# Motor3_PCIe.net
KiCad netlist of a schematic drawn in Altium Designer
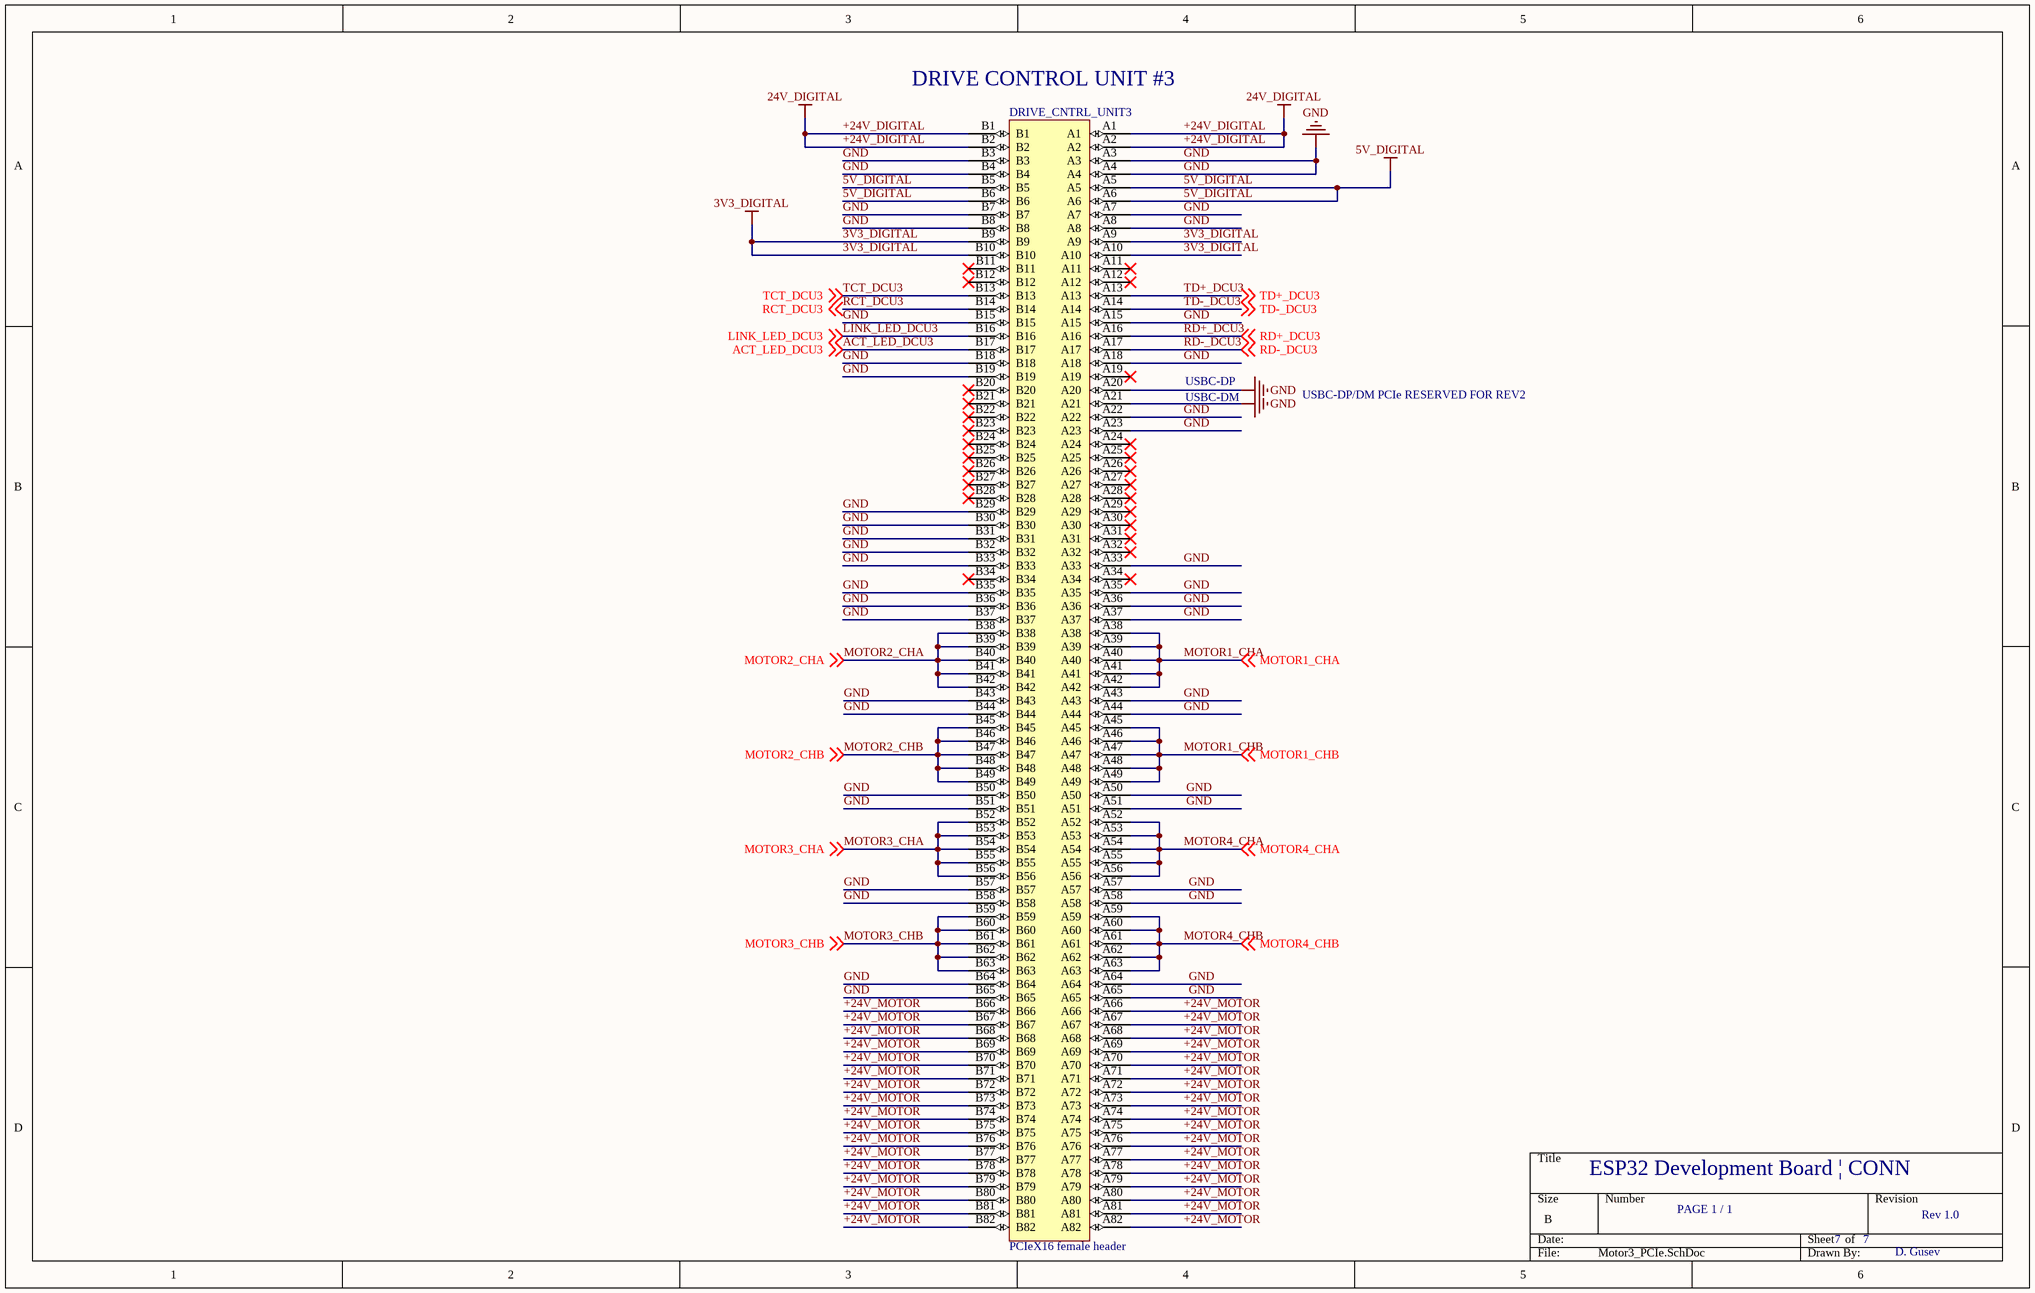
[diagram p0: Motor3_PCIe.SchDoc]

(export (version "E")
  (design (tool "Eeschema 10.0.6"))
  (components
    (comp (ref "DRIVE_CNTRL_UNIT3")
      (value "PCIeX16 female header")
      (footprint "SAMTEC_PCIE-164-02-X-D-TH")
      (description "164-position SAMTEC female header")
      (libsource (lib "ANTS-MotherBoard-B1") (part "PCIeX16 female header"))
    )
  )
  (nets
    (net (code "1") (name "/+24V_MOTOR") (class "Default")
      (node (ref "DRIVE_CNTRL_UNIT3") (pin "A66") (pinfunction "A66_A66") (pintype "bidirectional"))
      (node (ref "DRIVE_CNTRL_UNIT3") (pin "A67") (pinfunction "A67_A67") (pintype "bidirectional"))
      (node (ref "DRIVE_CNTRL_UNIT3") (pin "A68") (pinfunction "A68_A68") (pintype "bidirectional"))
      (node (ref "DRIVE_CNTRL_UNIT3") (pin "A69") (pinfunction "A69_A69") (pintype "bidirectional"))
      (node (ref "DRIVE_CNTRL_UNIT3") (pin "A70") (pinfunction "A70_A70") (pintype "bidirectional"))
      (node (ref "DRIVE_CNTRL_UNIT3") (pin "A71") (pinfunction "A71_A71") (pintype "bidirectional"))
      (node (ref "DRIVE_CNTRL_UNIT3") (pin "A72") (pinfunction "A72_A72") (pintype "bidirectional"))
      (node (ref "DRIVE_CNTRL_UNIT3") (pin "A73") (pinfunction "A73_A73") (pintype "bidirectional"))
      (node (ref "DRIVE_CNTRL_UNIT3") (pin "A74") (pinfunction "A74_A74") (pintype "bidirectional"))
      (node (ref "DRIVE_CNTRL_UNIT3") (pin "A75") (pinfunction "A75_A75") (pintype "bidirectional"))
      (node (ref "DRIVE_CNTRL_UNIT3") (pin "A76") (pinfunction "A76_A76") (pintype "bidirectional"))
      (node (ref "DRIVE_CNTRL_UNIT3") (pin "A77") (pinfunction "A77_A77") (pintype "bidirectional"))
      (node (ref "DRIVE_CNTRL_UNIT3") (pin "A78") (pinfunction "A78_A78") (pintype "bidirectional"))
      (node (ref "DRIVE_CNTRL_UNIT3") (pin "A79") (pinfunction "A79_A79") (pintype "bidirectional"))
      (node (ref "DRIVE_CNTRL_UNIT3") (pin "A80") (pinfunction "A80_A80") (pintype "bidirectional"))
      (node (ref "DRIVE_CNTRL_UNIT3") (pin "A81") (pinfunction "A81_A81") (pintype "bidirectional"))
      (node (ref "DRIVE_CNTRL_UNIT3") (pin "A82") (pinfunction "A82_A82") (pintype "bidirectional"))
      (node (ref "DRIVE_CNTRL_UNIT3") (pin "B66") (pinfunction "B66_B66") (pintype "bidirectional"))
      (node (ref "DRIVE_CNTRL_UNIT3") (pin "B67") (pinfunction "B67_B67") (pintype "bidirectional"))
      (node (ref "DRIVE_CNTRL_UNIT3") (pin "B68") (pinfunction "B68_B68") (pintype "bidirectional"))
      (node (ref "DRIVE_CNTRL_UNIT3") (pin "B69") (pinfunction "B69_B69") (pintype "bidirectional"))
      (node (ref "DRIVE_CNTRL_UNIT3") (pin "B70") (pinfunction "B70_B70") (pintype "bidirectional"))
      (node (ref "DRIVE_CNTRL_UNIT3") (pin "B71") (pinfunction "B71_B71") (pintype "bidirectional"))
      (node (ref "DRIVE_CNTRL_UNIT3") (pin "B72") (pinfunction "B72_B72") (pintype "bidirectional"))
      (node (ref "DRIVE_CNTRL_UNIT3") (pin "B73") (pinfunction "B73_B73") (pintype "bidirectional"))
      (node (ref "DRIVE_CNTRL_UNIT3") (pin "B74") (pinfunction "B74_B74") (pintype "bidirectional"))
      (node (ref "DRIVE_CNTRL_UNIT3") (pin "B75") (pinfunction "B75_B75") (pintype "bidirectional"))
      (node (ref "DRIVE_CNTRL_UNIT3") (pin "B76") (pinfunction "B76_B76") (pintype "bidirectional"))
      (node (ref "DRIVE_CNTRL_UNIT3") (pin "B77") (pinfunction "B77_B77") (pintype "bidirectional"))
      (node (ref "DRIVE_CNTRL_UNIT3") (pin "B78") (pinfunction "B78_B78") (pintype "bidirectional"))
      (node (ref "DRIVE_CNTRL_UNIT3") (pin "B79") (pinfunction "B79_B79") (pintype "bidirectional"))
      (node (ref "DRIVE_CNTRL_UNIT3") (pin "B80") (pinfunction "B80_B80") (pintype "bidirectional"))
      (node (ref "DRIVE_CNTRL_UNIT3") (pin "B81") (pinfunction "B81_B81") (pintype "bidirectional"))
      (node (ref "DRIVE_CNTRL_UNIT3") (pin "B82") (pinfunction "B82_B82") (pintype "bidirectional"))
    )
    (net (code "2") (name "3V3_DIGITAL") (class "Default")
      (node (ref "DRIVE_CNTRL_UNIT3") (pin "A10") (pinfunction "A10_A10") (pintype "bidirectional"))
      (node (ref "DRIVE_CNTRL_UNIT3") (pin "A9") (pinfunction "A9_A9") (pintype "bidirectional"))
      (node (ref "DRIVE_CNTRL_UNIT3") (pin "B10") (pinfunction "B10_B10") (pintype "bidirectional"))
      (node (ref "DRIVE_CNTRL_UNIT3") (pin "B9") (pinfunction "B9_B9") (pintype "bidirectional"))
    )
    (net (code "3") (name "5V_DIGITAL") (class "Default")
      (node (ref "DRIVE_CNTRL_UNIT3") (pin "A5") (pinfunction "A5_A5") (pintype "bidirectional"))
      (node (ref "DRIVE_CNTRL_UNIT3") (pin "A6") (pinfunction "A6_A6") (pintype "bidirectional"))
      (node (ref "DRIVE_CNTRL_UNIT3") (pin "B5") (pinfunction "B5_B5") (pintype "bidirectional"))
      (node (ref "DRIVE_CNTRL_UNIT3") (pin "B6") (pinfunction "B6_B6") (pintype "bidirectional"))
    )
    (net (code "4") (name "24V_DIGITAL") (class "Default")
      (node (ref "DRIVE_CNTRL_UNIT3") (pin "A1") (pinfunction "A1_A1") (pintype "bidirectional"))
      (node (ref "DRIVE_CNTRL_UNIT3") (pin "A2") (pinfunction "A2_A2") (pintype "bidirectional"))
      (node (ref "DRIVE_CNTRL_UNIT3") (pin "B1") (pinfunction "B1_B1") (pintype "bidirectional"))
      (node (ref "DRIVE_CNTRL_UNIT3") (pin "B2") (pinfunction "B2_B2") (pintype "bidirectional"))
    )
    (net (code "5") (name "ACT_LED_DCU3") (class "Default")
      (node (ref "DRIVE_CNTRL_UNIT3") (pin "B17") (pinfunction "B17_B17") (pintype "bidirectional"))
    )
    (net (code "6") (name "GND") (class "Default")
      (node (ref "DRIVE_CNTRL_UNIT3") (pin "A15") (pinfunction "A15_A15") (pintype "bidirectional"))
      (node (ref "DRIVE_CNTRL_UNIT3") (pin "A18") (pinfunction "A18_A18") (pintype "bidirectional"))
      (node (ref "DRIVE_CNTRL_UNIT3") (pin "A20") (pinfunction "A20_A20") (pintype "bidirectional"))
      (node (ref "DRIVE_CNTRL_UNIT3") (pin "A21") (pinfunction "A21_A21") (pintype "bidirectional"))
      (node (ref "DRIVE_CNTRL_UNIT3") (pin "A22") (pinfunction "A22_A22") (pintype "bidirectional"))
      (node (ref "DRIVE_CNTRL_UNIT3") (pin "A23") (pinfunction "A23_A23") (pintype "bidirectional"))
      (node (ref "DRIVE_CNTRL_UNIT3") (pin "A3") (pinfunction "A3_A3") (pintype "bidirectional"))
      (node (ref "DRIVE_CNTRL_UNIT3") (pin "A33") (pinfunction "A33_A33") (pintype "bidirectional"))
      (node (ref "DRIVE_CNTRL_UNIT3") (pin "A35") (pinfunction "A35_A35") (pintype "bidirectional"))
      (node (ref "DRIVE_CNTRL_UNIT3") (pin "A36") (pinfunction "A36_A36") (pintype "bidirectional"))
      (node (ref "DRIVE_CNTRL_UNIT3") (pin "A37") (pinfunction "A37_A37") (pintype "bidirectional"))
      (node (ref "DRIVE_CNTRL_UNIT3") (pin "A4") (pinfunction "A4_A4") (pintype "bidirectional"))
      (node (ref "DRIVE_CNTRL_UNIT3") (pin "A43") (pinfunction "A43_A43") (pintype "bidirectional"))
      (node (ref "DRIVE_CNTRL_UNIT3") (pin "A44") (pinfunction "A44_A44") (pintype "bidirectional"))
      (node (ref "DRIVE_CNTRL_UNIT3") (pin "A50") (pinfunction "A50_A50") (pintype "bidirectional"))
      (node (ref "DRIVE_CNTRL_UNIT3") (pin "A51") (pinfunction "A51_A51") (pintype "bidirectional"))
      (node (ref "DRIVE_CNTRL_UNIT3") (pin "A57") (pinfunction "A57_A57") (pintype "bidirectional"))
      (node (ref "DRIVE_CNTRL_UNIT3") (pin "A58") (pinfunction "A58_A58") (pintype "bidirectional"))
      (node (ref "DRIVE_CNTRL_UNIT3") (pin "A64") (pinfunction "A64_A64") (pintype "bidirectional"))
      (node (ref "DRIVE_CNTRL_UNIT3") (pin "A65") (pinfunction "A65_A65") (pintype "bidirectional"))
      (node (ref "DRIVE_CNTRL_UNIT3") (pin "A7") (pinfunction "A7_A7") (pintype "bidirectional"))
      (node (ref "DRIVE_CNTRL_UNIT3") (pin "A8") (pinfunction "A8_A8") (pintype "bidirectional"))
      (node (ref "DRIVE_CNTRL_UNIT3") (pin "B15") (pinfunction "B15_B15") (pintype "bidirectional"))
      (node (ref "DRIVE_CNTRL_UNIT3") (pin "B18") (pinfunction "B18_B18") (pintype "bidirectional"))
      (node (ref "DRIVE_CNTRL_UNIT3") (pin "B19") (pinfunction "B19_B19") (pintype "bidirectional"))
      (node (ref "DRIVE_CNTRL_UNIT3") (pin "B29") (pinfunction "B29_B29") (pintype "bidirectional"))
      (node (ref "DRIVE_CNTRL_UNIT3") (pin "B3") (pinfunction "B3_B3") (pintype "bidirectional"))
      (node (ref "DRIVE_CNTRL_UNIT3") (pin "B30") (pinfunction "B30_B30") (pintype "bidirectional"))
      (node (ref "DRIVE_CNTRL_UNIT3") (pin "B31") (pinfunction "B31_B31") (pintype "bidirectional"))
      (node (ref "DRIVE_CNTRL_UNIT3") (pin "B32") (pinfunction "B32_B32") (pintype "bidirectional"))
      (node (ref "DRIVE_CNTRL_UNIT3") (pin "B33") (pinfunction "B33_B33") (pintype "bidirectional"))
      (node (ref "DRIVE_CNTRL_UNIT3") (pin "B35") (pinfunction "B35_B35") (pintype "bidirectional"))
      (node (ref "DRIVE_CNTRL_UNIT3") (pin "B36") (pinfunction "B36_B36") (pintype "bidirectional"))
      (node (ref "DRIVE_CNTRL_UNIT3") (pin "B37") (pinfunction "B37_B37") (pintype "bidirectional"))
      (node (ref "DRIVE_CNTRL_UNIT3") (pin "B4") (pinfunction "B4_B4") (pintype "bidirectional"))
      (node (ref "DRIVE_CNTRL_UNIT3") (pin "B43") (pinfunction "B43_B43") (pintype "bidirectional"))
      (node (ref "DRIVE_CNTRL_UNIT3") (pin "B44") (pinfunction "B44_B44") (pintype "bidirectional"))
      (node (ref "DRIVE_CNTRL_UNIT3") (pin "B50") (pinfunction "B50_B50") (pintype "bidirectional"))
      (node (ref "DRIVE_CNTRL_UNIT3") (pin "B51") (pinfunction "B51_B51") (pintype "bidirectional"))
      (node (ref "DRIVE_CNTRL_UNIT3") (pin "B57") (pinfunction "B57_B57") (pintype "bidirectional"))
      (node (ref "DRIVE_CNTRL_UNIT3") (pin "B58") (pinfunction "B58_B58") (pintype "bidirectional"))
      (node (ref "DRIVE_CNTRL_UNIT3") (pin "B64") (pinfunction "B64_B64") (pintype "bidirectional"))
      (node (ref "DRIVE_CNTRL_UNIT3") (pin "B65") (pinfunction "B65_B65") (pintype "bidirectional"))
      (node (ref "DRIVE_CNTRL_UNIT3") (pin "B7") (pinfunction "B7_B7") (pintype "bidirectional"))
      (node (ref "DRIVE_CNTRL_UNIT3") (pin "B8") (pinfunction "B8_B8") (pintype "bidirectional"))
    )
    (net (code "7") (name "LINK_LED_DCU3") (class "Default")
      (node (ref "DRIVE_CNTRL_UNIT3") (pin "B16") (pinfunction "B16_B16") (pintype "bidirectional"))
    )
    (net (code "8") (name "MOTOR1_CHA") (class "Default")
      (node (ref "DRIVE_CNTRL_UNIT3") (pin "A38") (pinfunction "A38_A38") (pintype "bidirectional"))
      (node (ref "DRIVE_CNTRL_UNIT3") (pin "A39") (pinfunction "A39_A39") (pintype "bidirectional"))
      (node (ref "DRIVE_CNTRL_UNIT3") (pin "A40") (pinfunction "A40_A40") (pintype "bidirectional"))
      (node (ref "DRIVE_CNTRL_UNIT3") (pin "A41") (pinfunction "A41_A41") (pintype "bidirectional"))
      (node (ref "DRIVE_CNTRL_UNIT3") (pin "A42") (pinfunction "A42_A42") (pintype "bidirectional"))
    )
    (net (code "9") (name "MOTOR1_CHB") (class "Default")
      (node (ref "DRIVE_CNTRL_UNIT3") (pin "A45") (pinfunction "A45_A45") (pintype "bidirectional"))
      (node (ref "DRIVE_CNTRL_UNIT3") (pin "A46") (pinfunction "A46_A46") (pintype "bidirectional"))
      (node (ref "DRIVE_CNTRL_UNIT3") (pin "A47") (pinfunction "A47_A47") (pintype "bidirectional"))
      (node (ref "DRIVE_CNTRL_UNIT3") (pin "A48") (pinfunction "A48_A48") (pintype "bidirectional"))
      (node (ref "DRIVE_CNTRL_UNIT3") (pin "A49") (pinfunction "A49_A49") (pintype "bidirectional"))
    )
    (net (code "10") (name "MOTOR2_CHA") (class "Default")
      (node (ref "DRIVE_CNTRL_UNIT3") (pin "B38") (pinfunction "B38_B38") (pintype "bidirectional"))
      (node (ref "DRIVE_CNTRL_UNIT3") (pin "B39") (pinfunction "B39_B39") (pintype "bidirectional"))
      (node (ref "DRIVE_CNTRL_UNIT3") (pin "B40") (pinfunction "B40_B40") (pintype "bidirectional"))
      (node (ref "DRIVE_CNTRL_UNIT3") (pin "B41") (pinfunction "B41_B41") (pintype "bidirectional"))
      (node (ref "DRIVE_CNTRL_UNIT3") (pin "B42") (pinfunction "B42_B42") (pintype "bidirectional"))
    )
    (net (code "11") (name "MOTOR2_CHB") (class "Default")
      (node (ref "DRIVE_CNTRL_UNIT3") (pin "B45") (pinfunction "B45_B45") (pintype "bidirectional"))
      (node (ref "DRIVE_CNTRL_UNIT3") (pin "B46") (pinfunction "B46_B46") (pintype "bidirectional"))
      (node (ref "DRIVE_CNTRL_UNIT3") (pin "B47") (pinfunction "B47_B47") (pintype "bidirectional"))
      (node (ref "DRIVE_CNTRL_UNIT3") (pin "B48") (pinfunction "B48_B48") (pintype "bidirectional"))
      (node (ref "DRIVE_CNTRL_UNIT3") (pin "B49") (pinfunction "B49_B49") (pintype "bidirectional"))
    )
    (net (code "12") (name "MOTOR3_CHA") (class "Default")
      (node (ref "DRIVE_CNTRL_UNIT3") (pin "B52") (pinfunction "B52_B52") (pintype "bidirectional"))
      (node (ref "DRIVE_CNTRL_UNIT3") (pin "B53") (pinfunction "B53_B53") (pintype "bidirectional"))
      (node (ref "DRIVE_CNTRL_UNIT3") (pin "B54") (pinfunction "B54_B54") (pintype "bidirectional"))
      (node (ref "DRIVE_CNTRL_UNIT3") (pin "B55") (pinfunction "B55_B55") (pintype "bidirectional"))
      (node (ref "DRIVE_CNTRL_UNIT3") (pin "B56") (pinfunction "B56_B56") (pintype "bidirectional"))
    )
    (net (code "13") (name "MOTOR3_CHB") (class "Default")
      (node (ref "DRIVE_CNTRL_UNIT3") (pin "B59") (pinfunction "B59_B59") (pintype "bidirectional"))
      (node (ref "DRIVE_CNTRL_UNIT3") (pin "B60") (pinfunction "B60_B60") (pintype "bidirectional"))
      (node (ref "DRIVE_CNTRL_UNIT3") (pin "B61") (pinfunction "B61_B61") (pintype "bidirectional"))
      (node (ref "DRIVE_CNTRL_UNIT3") (pin "B62") (pinfunction "B62_B62") (pintype "bidirectional"))
      (node (ref "DRIVE_CNTRL_UNIT3") (pin "B63") (pinfunction "B63_B63") (pintype "bidirectional"))
    )
    (net (code "14") (name "MOTOR4_CHA") (class "Default")
      (node (ref "DRIVE_CNTRL_UNIT3") (pin "A52") (pinfunction "A52_A52") (pintype "bidirectional"))
      (node (ref "DRIVE_CNTRL_UNIT3") (pin "A53") (pinfunction "A53_A53") (pintype "bidirectional"))
      (node (ref "DRIVE_CNTRL_UNIT3") (pin "A54") (pinfunction "A54_A54") (pintype "bidirectional"))
      (node (ref "DRIVE_CNTRL_UNIT3") (pin "A55") (pinfunction "A55_A55") (pintype "bidirectional"))
      (node (ref "DRIVE_CNTRL_UNIT3") (pin "A56") (pinfunction "A56_A56") (pintype "bidirectional"))
    )
    (net (code "15") (name "MOTOR4_CHB") (class "Default")
      (node (ref "DRIVE_CNTRL_UNIT3") (pin "A59") (pinfunction "A59_A59") (pintype "bidirectional"))
      (node (ref "DRIVE_CNTRL_UNIT3") (pin "A60") (pinfunction "A60_A60") (pintype "bidirectional"))
      (node (ref "DRIVE_CNTRL_UNIT3") (pin "A61") (pinfunction "A61_A61") (pintype "bidirectional"))
      (node (ref "DRIVE_CNTRL_UNIT3") (pin "A62") (pinfunction "A62_A62") (pintype "bidirectional"))
      (node (ref "DRIVE_CNTRL_UNIT3") (pin "A63") (pinfunction "A63_A63") (pintype "bidirectional"))
    )
    (net (code "16") (name "RCT_DCU3") (class "Default")
      (node (ref "DRIVE_CNTRL_UNIT3") (pin "B14") (pinfunction "B14_B14") (pintype "bidirectional"))
    )
    (net (code "17") (name "RD+_DCU3") (class "Default")
      (node (ref "DRIVE_CNTRL_UNIT3") (pin "A16") (pinfunction "A16_A16") (pintype "bidirectional"))
    )
    (net (code "18") (name "RD-_DCU3") (class "Default")
      (node (ref "DRIVE_CNTRL_UNIT3") (pin "A17") (pinfunction "A17_A17") (pintype "bidirectional"))
    )
    (net (code "19") (name "TCT_DCU3") (class "Default")
      (node (ref "DRIVE_CNTRL_UNIT3") (pin "B13") (pinfunction "B13_B13") (pintype "bidirectional"))
    )
    (net (code "20") (name "TD+_DCU3") (class "Default")
      (node (ref "DRIVE_CNTRL_UNIT3") (pin "A13") (pinfunction "A13_A13") (pintype "bidirectional"))
    )
    (net (code "21") (name "TD-_DCU3") (class "Default")
      (node (ref "DRIVE_CNTRL_UNIT3") (pin "A14") (pinfunction "A14_A14") (pintype "bidirectional"))
    )
    (net (code "22") (name "unconnected-(DRIVE_CNTRL_UNIT3-PadA11)") (class "Default")
      (node (ref "DRIVE_CNTRL_UNIT3") (pin "A11") (pinfunction "A11_A11") (pintype "bidirectional+no_connect"))
    )
    (net (code "23") (name "unconnected-(DRIVE_CNTRL_UNIT3-PadA12)") (class "Default")
      (node (ref "DRIVE_CNTRL_UNIT3") (pin "A12") (pinfunction "A12_A12") (pintype "bidirectional+no_connect"))
    )
    (net (code "24") (name "unconnected-(DRIVE_CNTRL_UNIT3-PadA19)") (class "Default")
      (node (ref "DRIVE_CNTRL_UNIT3") (pin "A19") (pinfunction "A19_A19") (pintype "bidirectional+no_connect"))
    )
    (net (code "25") (name "unconnected-(DRIVE_CNTRL_UNIT3-PadA24)") (class "Default")
      (node (ref "DRIVE_CNTRL_UNIT3") (pin "A24") (pinfunction "A24_A24") (pintype "bidirectional+no_connect"))
    )
    (net (code "26") (name "unconnected-(DRIVE_CNTRL_UNIT3-PadA25)") (class "Default")
      (node (ref "DRIVE_CNTRL_UNIT3") (pin "A25") (pinfunction "A25_A25") (pintype "bidirectional+no_connect"))
    )
    (net (code "27") (name "unconnected-(DRIVE_CNTRL_UNIT3-PadA26)") (class "Default")
      (node (ref "DRIVE_CNTRL_UNIT3") (pin "A26") (pinfunction "A26_A26") (pintype "bidirectional+no_connect"))
    )
    (net (code "28") (name "unconnected-(DRIVE_CNTRL_UNIT3-PadA27)") (class "Default")
      (node (ref "DRIVE_CNTRL_UNIT3") (pin "A27") (pinfunction "A27_A27") (pintype "bidirectional+no_connect"))
    )
    (net (code "29") (name "unconnected-(DRIVE_CNTRL_UNIT3-PadA28)") (class "Default")
      (node (ref "DRIVE_CNTRL_UNIT3") (pin "A28") (pinfunction "A28_A28") (pintype "bidirectional+no_connect"))
    )
    (net (code "30") (name "unconnected-(DRIVE_CNTRL_UNIT3-PadA29)") (class "Default")
      (node (ref "DRIVE_CNTRL_UNIT3") (pin "A29") (pinfunction "A29_A29") (pintype "bidirectional+no_connect"))
    )
    (net (code "31") (name "unconnected-(DRIVE_CNTRL_UNIT3-PadA30)") (class "Default")
      (node (ref "DRIVE_CNTRL_UNIT3") (pin "A30") (pinfunction "A30_A30") (pintype "bidirectional+no_connect"))
    )
    (net (code "32") (name "unconnected-(DRIVE_CNTRL_UNIT3-PadA31)") (class "Default")
      (node (ref "DRIVE_CNTRL_UNIT3") (pin "A31") (pinfunction "A31_A31") (pintype "bidirectional+no_connect"))
    )
    (net (code "33") (name "unconnected-(DRIVE_CNTRL_UNIT3-PadA32)") (class "Default")
      (node (ref "DRIVE_CNTRL_UNIT3") (pin "A32") (pinfunction "A32_A32") (pintype "bidirectional+no_connect"))
    )
    (net (code "34") (name "unconnected-(DRIVE_CNTRL_UNIT3-PadA34)") (class "Default")
      (node (ref "DRIVE_CNTRL_UNIT3") (pin "A34") (pinfunction "A34_A34") (pintype "bidirectional+no_connect"))
    )
    (net (code "35") (name "unconnected-(DRIVE_CNTRL_UNIT3-PadB11)") (class "Default")
      (node (ref "DRIVE_CNTRL_UNIT3") (pin "B11") (pinfunction "B11_B11") (pintype "bidirectional+no_connect"))
    )
    (net (code "36") (name "unconnected-(DRIVE_CNTRL_UNIT3-PadB12)") (class "Default")
      (node (ref "DRIVE_CNTRL_UNIT3") (pin "B12") (pinfunction "B12_B12") (pintype "bidirectional+no_connect"))
    )
    (net (code "37") (name "unconnected-(DRIVE_CNTRL_UNIT3-PadB20)") (class "Default")
      (node (ref "DRIVE_CNTRL_UNIT3") (pin "B20") (pinfunction "B20_B20") (pintype "bidirectional+no_connect"))
    )
    (net (code "38") (name "unconnected-(DRIVE_CNTRL_UNIT3-PadB21)") (class "Default")
      (node (ref "DRIVE_CNTRL_UNIT3") (pin "B21") (pinfunction "B21_B21") (pintype "bidirectional+no_connect"))
    )
    (net (code "39") (name "unconnected-(DRIVE_CNTRL_UNIT3-PadB22)") (class "Default")
      (node (ref "DRIVE_CNTRL_UNIT3") (pin "B22") (pinfunction "B22_B22") (pintype "bidirectional+no_connect"))
    )
    (net (code "40") (name "unconnected-(DRIVE_CNTRL_UNIT3-PadB23)") (class "Default")
      (node (ref "DRIVE_CNTRL_UNIT3") (pin "B23") (pinfunction "B23_B23") (pintype "bidirectional+no_connect"))
    )
    (net (code "41") (name "unconnected-(DRIVE_CNTRL_UNIT3-PadB24)") (class "Default")
      (node (ref "DRIVE_CNTRL_UNIT3") (pin "B24") (pinfunction "B24_B24") (pintype "bidirectional+no_connect"))
    )
    (net (code "42") (name "unconnected-(DRIVE_CNTRL_UNIT3-PadB25)") (class "Default")
      (node (ref "DRIVE_CNTRL_UNIT3") (pin "B25") (pinfunction "B25_B25") (pintype "bidirectional+no_connect"))
    )
    (net (code "43") (name "unconnected-(DRIVE_CNTRL_UNIT3-PadB26)") (class "Default")
      (node (ref "DRIVE_CNTRL_UNIT3") (pin "B26") (pinfunction "B26_B26") (pintype "bidirectional+no_connect"))
    )
    (net (code "44") (name "unconnected-(DRIVE_CNTRL_UNIT3-PadB27)") (class "Default")
      (node (ref "DRIVE_CNTRL_UNIT3") (pin "B27") (pinfunction "B27_B27") (pintype "bidirectional+no_connect"))
    )
    (net (code "45") (name "unconnected-(DRIVE_CNTRL_UNIT3-PadB28)") (class "Default")
      (node (ref "DRIVE_CNTRL_UNIT3") (pin "B28") (pinfunction "B28_B28") (pintype "bidirectional+no_connect"))
    )
    (net (code "46") (name "unconnected-(DRIVE_CNTRL_UNIT3-PadB34)") (class "Default")
      (node (ref "DRIVE_CNTRL_UNIT3") (pin "B34") (pinfunction "B34_B34") (pintype "bidirectional+no_connect"))
    )
  )
)
